# 07_ONB_COMPASS.net
KiCad netlist of a schematic drawn in Altium Designer
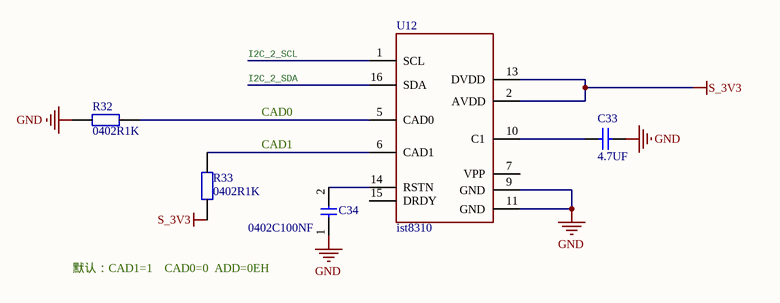
[diagram p0: 07_ONB_COMPASS.SchDoc]

(export (version "E")
  (design (tool "Eeschema 10.0.6"))
  (components
    (comp (ref "C33")
      (value "4.7UF")
      (description "Capacitor")
      (libsource (lib "Miscellaneous Devices") (part "Cap"))
    )
    (comp (ref "C34")
      (value "0402C100NF")
      (footprint "0402C")
      (description "50V 5%")
      (libsource (lib "CUAV") (part "0402C100NF"))
    )
    (comp (ref "R32")
      (value "0402R1K")
      (footprint "0402R")
      (description "0402R1K 1%")
      (libsource (lib "CUAV") (part "0402R1K"))
    )
    (comp (ref "R33")
      (value "0402R1K")
      (footprint "0402R")
      (description "0402R1K 1%")
      (libsource (lib "") (part "0402R1K_1"))
    )
    (comp (ref "U12") (value "ist8310") (footprint "LGA16_4X4") (libsource (lib "CUAV") (part "ist8310")))
  )
  (nets
    (net (code "1") (name "/CAD0") (class "Default")
      (node (ref "R32") (pin "1") (pintype "passive"))
      (node (ref "U12") (pin "5") (pinfunction "CAD0_5") (pintype "passive"))
    )
    (net (code "2") (name "/CAD1") (class "Default")
      (node (ref "R33") (pin "2") (pintype "passive"))
      (node (ref "U12") (pin "6") (pinfunction "CAD1_6") (pintype "passive"))
    )
    (net (code "3") (name "/I2C_2_SCL") (class "Default")
      (node (ref "U12") (pin "1") (pinfunction "SCL_1") (pintype "passive"))
    )
    (net (code "4") (name "/I2C_2_SDA") (class "Default")
      (node (ref "U12") (pin "16") (pinfunction "SDA_16") (pintype "passive"))
    )
    (net (code "6") (name "GND") (class "Default")
      (node (ref "C33") (pin "2") (pinfunction "2_2") (pintype "passive"))
      (node (ref "C34") (pin "1") (pintype "passive"))
      (node (ref "R32") (pin "2") (pintype "passive"))
      (node (ref "U12") (pin "11") (pinfunction "GND_11") (pintype "passive"))
      (node (ref "U12") (pin "9") (pinfunction "GND_9") (pintype "passive"))
    )
    (net (code "7") (name "Net-(U12-C1)") (class "Default")
      (node (ref "C33") (pin "1") (pinfunction "1_1") (pintype "passive"))
      (node (ref "U12") (pin "10") (pinfunction "C1_10") (pintype "passive"))
    )
    (net (code "8") (name "Net-(U12-RSTN)") (class "Default")
      (node (ref "C34") (pin "2") (pintype "passive"))
      (node (ref "U12") (pin "14") (pinfunction "RSTN_14") (pintype "passive"))
    )
    (net (code "9") (name "S_3V3") (class "Default")
      (node (ref "R33") (pin "1") (pintype "passive"))
      (node (ref "U12") (pin "13") (pinfunction "DVDD_13") (pintype "passive"))
      (node (ref "U12") (pin "2") (pinfunction "AVDD_2") (pintype "passive"))
    )
    (net (code "10") (name "unconnected-(U12-DRDY-Pad15)") (class "Default")
      (node (ref "U12") (pin "15") (pinfunction "DRDY_15") (pintype "passive"))
    )
    (net (code "11") (name "unconnected-(U12-VPP-Pad7)") (class "Default")
      (node (ref "U12") (pin "7") (pinfunction "VPP_7") (pintype "passive"))
    )
  )
)
